# 04_GAP9_CHIP_MEM.net
KiCad netlist of a schematic drawn in Altium Designer
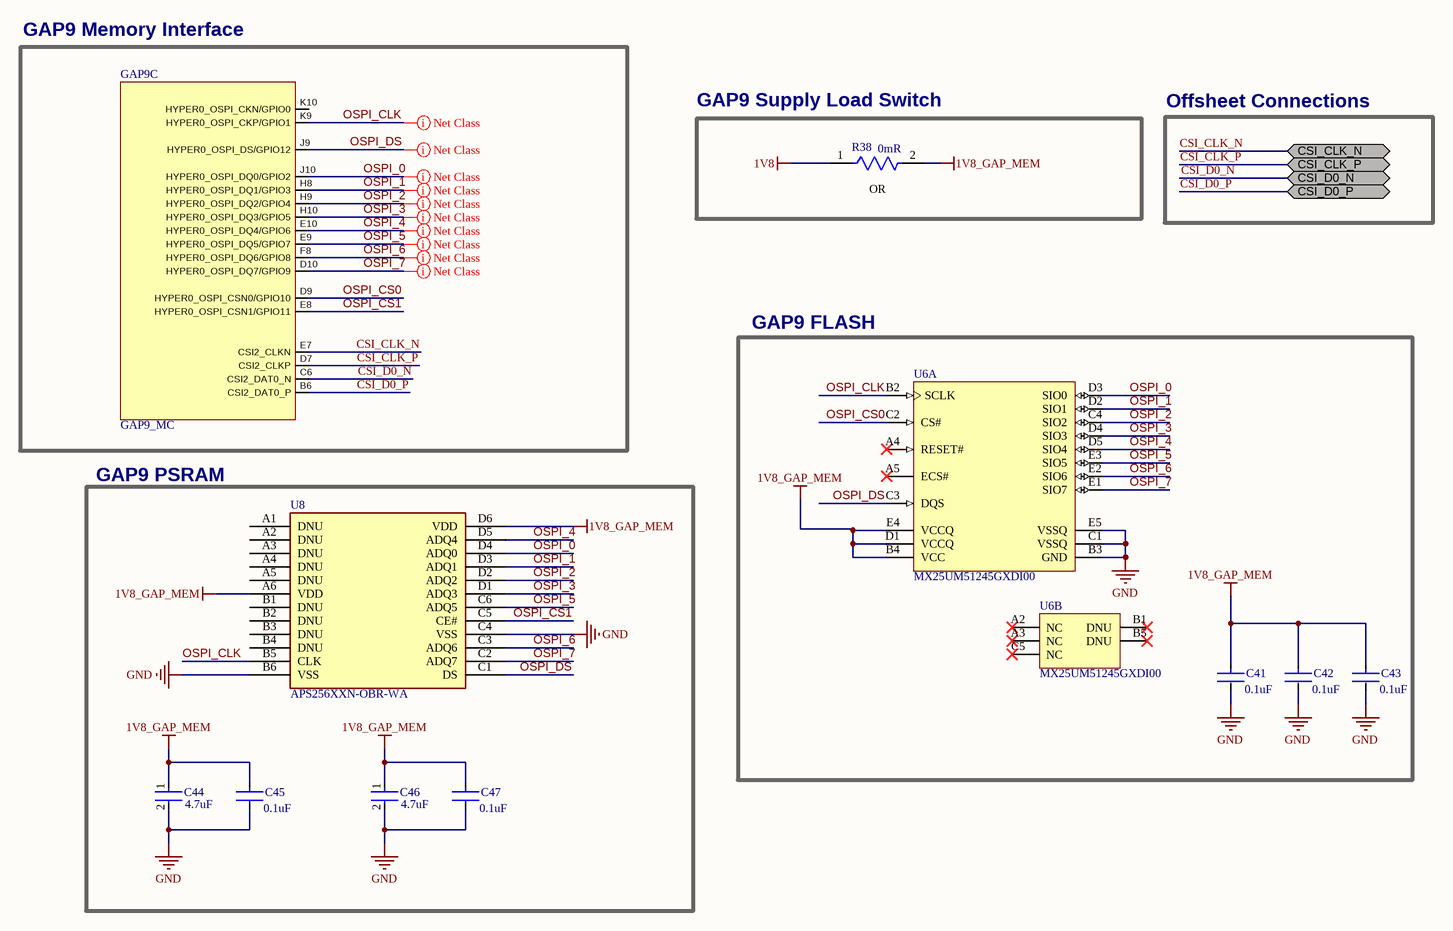
[diagram p0: 04_GAP9_CHIP_MEM.SchDoc]

(export (version "E")
  (design (tool "Eeschema 10.0.6"))
  (components
    (comp (ref "C41")
      (value "GRM033Z71C104KE14D")
      (footprint "FP-GRM033-0_03-IPC_B")
      (description "Chip Multilayer Ceramic Capacitors for General Purpose, 0201, 0.10uF, X7R, 15%, 10%, 16V")
      (fields (field (name "CAPACITANCE") "0.1uF"))
      (libsource (lib "Altium Content Vault") (part "b4654b650e69147ec39a6b967a45e02"))
    )
    (comp (ref "C42")
      (value "GRM033Z71C104KE14D")
      (footprint "FP-GRM033-0_03-IPC_B")
      (description "Chip Multilayer Ceramic Capacitors for General Purpose, 0201, 0.10uF, X7R, 15%, 10%, 16V")
      (fields (field (name "CAPACITANCE") "0.1uF"))
      (libsource (lib "Altium Content Vault") (part "b4654b650e69147ec39a6b967a45e02"))
    )
    (comp (ref "C43")
      (value "GRM033Z71C104KE14D")
      (footprint "FP-GRM033-0_03-IPC_B")
      (description "Chip Multilayer Ceramic Capacitors for General Purpose, 0201, 0.10uF, X7R, 15%, 10%, 16V")
      (fields (field (name "CAPACITANCE") "0.1uF"))
      (libsource (lib "Altium Content Vault") (part "b4654b650e69147ec39a6b967a45e02"))
    )
    (comp (ref "C44")
      (value "GRM035R60J475ME15D")
      (footprint "FP-GRM035-0_09-IPC_B")
      (description "Chip Multilayer Ceramic Capacitors for General Purpose, 0201, 4.7uF, X5R, 15%, 20%, 6.3V")
      (fields (field (name "CAPACITANCE") "4.7uF") (field (name "TOLERANCE") "20%"))
      (libsource (lib "Altium Content Vault") (part "02cd4be3c70576c341d710602a673aa"))
    )
    (comp (ref "C45")
      (value "GRM033Z71C104KE14D")
      (footprint "FP-GRM033-0_03-IPC_B")
      (description "Chip Multilayer Ceramic Capacitors for General Purpose, 0201, 0.10uF, X7R, 15%, 10%, 16V")
      (fields (field (name "CAPACITANCE") "0.1uF"))
      (libsource (lib "Altium Content Vault") (part "b4654b650e69147ec39a6b967a45e02"))
    )
    (comp (ref "C46")
      (value "GRM035R60J475ME15D")
      (footprint "FP-GRM035-0_09-IPC_B")
      (description "Chip Multilayer Ceramic Capacitors for General Purpose, 0201, 4.7uF, X5R, 15%, 20%, 6.3V")
      (fields (field (name "CAPACITANCE") "4.7uF") (field (name "TOLERANCE") "20%"))
      (libsource (lib "Altium Content Vault") (part "02cd4be3c70576c341d710602a673aa"))
    )
    (comp (ref "C47")
      (value "GRM033Z71C104KE14D")
      (footprint "FP-GRM033-0_03-IPC_B")
      (description "Chip Multilayer Ceramic Capacitors for General Purpose, 0201, 0.10uF, X7R, 15%, 10%, 16V")
      (fields (field (name "CAPACITANCE") "0.1uF"))
      (libsource (lib "Altium Content Vault") (part "b4654b650e69147ec39a6b967a45e02"))
    )
    (comp (ref "GAP9") (value "GAP9_MC") (footprint "GAP9") (libsource (lib "EEG_SchLib") (part "GAP9_MC")))
    (comp (ref "R38")
      (value "0mR")
      (footprint "FP-CRCW0402-e3-IPC_C")
      (description "RES Thick Film, 0Ω, 0.063W, 0402")
      (fields (field (name "TOLERANCE") "5%") (field (name "Comment") "CRCW04020000Z0ED"))
      (libsource (lib "Altium Content Vault") (part "1029c3af85768c4190bb7ad29bc67b5"))
    )
    (comp (ref "U6")
      (value "MX25UM51245GXDI00")
      (footprint "FBGA24_A-130")
      (description "NOR Flash Memory 512Mb 1.8V Octa I/O Serial 24-Pin BGA")
      (fields (field (name "MFR") "Macronix"))
      (libsource (lib "ETHZ Vault") (part "MX25UM51245GXDI00"))
    )
    (comp (ref "U8")
      (value "APS256XXN-OBR-WA")
      (footprint "WLCSP24")
      (description "No Description Available")
      (fields
        (field (name "MANUFACTURER_PART_NUMBER") "APS256XXN-OBR-BG")
        (field (name "COPYRIGHT") "Copyright (C) 2022 Ultra Librarian. All rights reserved.")
      )
      (libsource (lib "EEG_SchLib") (part "APS256XXN-OBR"))
    )
  )
  (nets
    (net (code "1") (name "/CSI_CLK_N") (class "Default")
      (node (ref "GAP9") (pin "E7") (pinfunction "CSI2_CLKN_E7") (pintype "passive"))
    )
    (net (code "2") (name "/CSI_CLK_P") (class "Default")
      (node (ref "GAP9") (pin "D7") (pinfunction "CSI2_CLKP_D7") (pintype "passive"))
    )
    (net (code "3") (name "/CSI_D0_N") (class "Default")
      (node (ref "GAP9") (pin "C6") (pinfunction "CSI2_DAT0_N_C6") (pintype "passive"))
    )
    (net (code "4") (name "/CSI_D0_P") (class "Default")
      (node (ref "GAP9") (pin "B6") (pinfunction "CSI2_DAT0_P_B6") (pintype "passive"))
    )
    (net (code "5") (name "/OSPI_0") (class "Default")
      (node (ref "GAP9") (pin "J10") (pinfunction "HYPER0_OSPI_DQ0/GPIO2_J10") (pintype "passive"))
      (node (ref "U6") (pin "D3") (pinfunction "SIO0_D3") (pintype "bidirectional"))
      (node (ref "U8") (pin "D4") (pinfunction "ADQ0_D4") (pintype "passive"))
    )
    (net (code "6") (name "/OSPI_1") (class "Default")
      (node (ref "GAP9") (pin "H8") (pinfunction "HYPER0_OSPI_DQ1/GPIO3_H8") (pintype "passive"))
      (node (ref "U6") (pin "D2") (pinfunction "SIO1_D2") (pintype "bidirectional"))
      (node (ref "U8") (pin "D3") (pinfunction "ADQ1_D3") (pintype "passive"))
    )
    (net (code "7") (name "/OSPI_2") (class "Default")
      (node (ref "GAP9") (pin "H9") (pinfunction "HYPER0_OSPI_DQ2/GPIO4_H9") (pintype "passive"))
      (node (ref "U6") (pin "C4") (pinfunction "SIO2_C4") (pintype "bidirectional"))
      (node (ref "U8") (pin "D2") (pinfunction "ADQ2_D2") (pintype "passive"))
    )
    (net (code "8") (name "/OSPI_3") (class "Default")
      (node (ref "GAP9") (pin "H10") (pinfunction "HYPER0_OSPI_DQ3/GPIO5_H10") (pintype "passive"))
      (node (ref "U6") (pin "D4") (pinfunction "SIO3_D4") (pintype "bidirectional"))
      (node (ref "U8") (pin "D1") (pinfunction "ADQ3_D1") (pintype "passive"))
    )
    (net (code "9") (name "/OSPI_4") (class "Default")
      (node (ref "GAP9") (pin "E10") (pinfunction "HYPER0_OSPI_DQ4/GPIO6_E10") (pintype "passive"))
      (node (ref "U6") (pin "D5") (pinfunction "SIO4_D5") (pintype "bidirectional"))
      (node (ref "U8") (pin "D5") (pinfunction "ADQ4_D5") (pintype "passive"))
    )
    (net (code "10") (name "/OSPI_5") (class "Default")
      (node (ref "GAP9") (pin "E9") (pinfunction "HYPER0_OSPI_DQ5/GPIO7_E9") (pintype "passive"))
      (node (ref "U6") (pin "E3") (pinfunction "SIO5_E3") (pintype "bidirectional"))
      (node (ref "U8") (pin "C6") (pinfunction "ADQ5_C6") (pintype "passive"))
    )
    (net (code "11") (name "/OSPI_6") (class "Default")
      (node (ref "GAP9") (pin "F8") (pinfunction "HYPER0_OSPI_DQ6/GPIO8_F8") (pintype "passive"))
      (node (ref "U6") (pin "E2") (pinfunction "SIO6_E2") (pintype "bidirectional"))
      (node (ref "U8") (pin "C3") (pinfunction "ADQ6_C3") (pintype "passive"))
    )
    (net (code "12") (name "/OSPI_7") (class "Default")
      (node (ref "GAP9") (pin "D10") (pinfunction "HYPER0_OSPI_DQ7/GPIO9_D10") (pintype "passive"))
      (node (ref "U6") (pin "E1") (pinfunction "SIO7_E1") (pintype "bidirectional"))
      (node (ref "U8") (pin "C2") (pinfunction "ADQ7_C2") (pintype "passive"))
    )
    (net (code "13") (name "/OSPI_CLK") (class "Default")
      (node (ref "GAP9") (pin "K9") (pinfunction "HYPER0_OSPI_CKP/GPIO1_K9") (pintype "passive"))
      (node (ref "U6") (pin "B2") (pinfunction "SCLK_B2") (pintype "input"))
      (node (ref "U8") (pin "B5") (pinfunction "CLK_B5") (pintype "passive"))
    )
    (net (code "14") (name "/OSPI_CS0") (class "Default")
      (node (ref "GAP9") (pin "D9") (pinfunction "HYPER0_OSPI_CSN0/GPIO10_D9") (pintype "passive"))
      (node (ref "U6") (pin "C2") (pinfunction "CS#_C2") (pintype "input"))
    )
    (net (code "15") (name "/OSPI_CS1") (class "Default")
      (node (ref "GAP9") (pin "E8") (pinfunction "HYPER0_OSPI_CSN1/GPIO11_E8") (pintype "passive"))
      (node (ref "U8") (pin "C5") (pinfunction "CE#_C5") (pintype "passive"))
    )
    (net (code "16") (name "/OSPI_DS") (class "Default")
      (node (ref "GAP9") (pin "J9") (pinfunction "HYPER0_OSPI_DS/GPIO12_J9") (pintype "passive"))
      (node (ref "U6") (pin "C3") (pinfunction "DQS_C3") (pintype "input"))
      (node (ref "U8") (pin "C1") (pinfunction "DS_C1") (pintype "passive"))
    )
    (net (code "17") (name "1V8") (class "Default")
      (node (ref "R38") (pin "1") (pinfunction "1_1") (pintype "passive"))
    )
    (net (code "18") (name "1V8_GAP_MEM") (class "Default")
      (node (ref "C41") (pin "1") (pinfunction "1_1") (pintype "passive"))
      (node (ref "C42") (pin "1") (pinfunction "1_1") (pintype "passive"))
      (node (ref "C43") (pin "1") (pinfunction "1_1") (pintype "passive"))
      (node (ref "C44") (pin "1") (pinfunction "1_1") (pintype "passive"))
      (node (ref "C45") (pin "1") (pinfunction "1_1") (pintype "passive"))
      (node (ref "C46") (pin "1") (pinfunction "1_1") (pintype "passive"))
      (node (ref "C47") (pin "1") (pinfunction "1_1") (pintype "passive"))
      (node (ref "R38") (pin "2") (pinfunction "2_2") (pintype "passive"))
      (node (ref "U6") (pin "B4") (pinfunction "VCC_B4") (pintype "power_in"))
      (node (ref "U6") (pin "D1") (pinfunction "VCCQ_D1") (pintype "power_in"))
      (node (ref "U6") (pin "E4") (pinfunction "VCCQ_E4") (pintype "power_in"))
      (node (ref "U8") (pin "A6") (pinfunction "VDD_A6") (pintype "passive"))
      (node (ref "U8") (pin "D6") (pinfunction "VDD_D6") (pintype "passive"))
    )
    (net (code "19") (name "GND") (class "Default")
      (node (ref "C41") (pin "2") (pinfunction "2_2") (pintype "passive"))
      (node (ref "C42") (pin "2") (pinfunction "2_2") (pintype "passive"))
      (node (ref "C43") (pin "2") (pinfunction "2_2") (pintype "passive"))
      (node (ref "C44") (pin "2") (pinfunction "2_2") (pintype "passive"))
      (node (ref "C45") (pin "2") (pinfunction "2_2") (pintype "passive"))
      (node (ref "C46") (pin "2") (pinfunction "2_2") (pintype "passive"))
      (node (ref "C47") (pin "2") (pinfunction "2_2") (pintype "passive"))
      (node (ref "U6") (pin "B3") (pinfunction "GND_B3") (pintype "power_in"))
      (node (ref "U6") (pin "C1") (pinfunction "VSSQ_C1") (pintype "power_in"))
      (node (ref "U6") (pin "E5") (pinfunction "VSSQ_E5") (pintype "power_in"))
      (node (ref "U8") (pin "B6") (pinfunction "VSS_B6") (pintype "passive"))
      (node (ref "U8") (pin "C4") (pinfunction "VSS_C4") (pintype "passive"))
    )
    (net (code "20") (name "unconnected-(GAP9C-HYPER0_OSPI_CKN{slash}GPIO0-PadK10)") (class "Default")
      (node (ref "GAP9") (pin "K10") (pinfunction "HYPER0_OSPI_CKN/GPIO0_K10") (pintype "passive"))
    )
    (net (code "21") (name "unconnected-(U6A-ECS#-PadA5)") (class "Default")
      (node (ref "U6") (pin "A5") (pinfunction "ECS#_A5") (pintype "open_collector+no_connect"))
    )
    (net (code "22") (name "unconnected-(U6A-RESET#-PadA4)") (class "Default")
      (node (ref "U6") (pin "A4") (pinfunction "RESET#_A4") (pintype "input+no_connect"))
    )
    (net (code "23") (name "unconnected-(U6B-DNU-PadB1)") (class "Default")
      (node (ref "U6") (pin "B1") (pinfunction "DNU_B1") (pintype "passive+no_connect"))
    )
    (net (code "24") (name "unconnected-(U6B-DNU-PadB5)") (class "Default")
      (node (ref "U6") (pin "B5") (pinfunction "DNU_B5") (pintype "passive+no_connect"))
    )
    (net (code "25") (name "unconnected-(U6B-NC-PadA2)") (class "Default")
      (node (ref "U6") (pin "A2") (pinfunction "NC_A2") (pintype "passive+no_connect"))
    )
    (net (code "26") (name "unconnected-(U6B-NC-PadA3)") (class "Default")
      (node (ref "U6") (pin "A3") (pinfunction "NC_A3") (pintype "passive+no_connect"))
    )
    (net (code "27") (name "unconnected-(U6B-NC-PadC5)") (class "Default")
      (node (ref "U6") (pin "C5") (pinfunction "NC_C5") (pintype "passive+no_connect"))
    )
    (net (code "28") (name "unconnected-(U8-DNU-PadA1)") (class "Default")
      (node (ref "U8") (pin "A1") (pinfunction "DNU_A1") (pintype "passive"))
    )
    (net (code "29") (name "unconnected-(U8-DNU-PadA2)") (class "Default")
      (node (ref "U8") (pin "A2") (pinfunction "DNU_A2") (pintype "passive"))
    )
    (net (code "30") (name "unconnected-(U8-DNU-PadA3)") (class "Default")
      (node (ref "U8") (pin "A3") (pinfunction "DNU_A3") (pintype "passive"))
    )
    (net (code "31") (name "unconnected-(U8-DNU-PadA4)") (class "Default")
      (node (ref "U8") (pin "A4") (pinfunction "DNU_A4") (pintype "passive"))
    )
    (net (code "32") (name "unconnected-(U8-DNU-PadA5)") (class "Default")
      (node (ref "U8") (pin "A5") (pinfunction "DNU_A5") (pintype "passive"))
    )
    (net (code "33") (name "unconnected-(U8-DNU-PadB1)") (class "Default")
      (node (ref "U8") (pin "B1") (pinfunction "DNU_B1") (pintype "passive"))
    )
    (net (code "34") (name "unconnected-(U8-DNU-PadB2)") (class "Default")
      (node (ref "U8") (pin "B2") (pinfunction "DNU_B2") (pintype "passive"))
    )
    (net (code "35") (name "unconnected-(U8-DNU-PadB3)") (class "Default")
      (node (ref "U8") (pin "B3") (pinfunction "DNU_B3") (pintype "passive"))
    )
    (net (code "36") (name "unconnected-(U8-DNU-PadB4)") (class "Default")
      (node (ref "U8") (pin "B4") (pinfunction "DNU_B4") (pintype "passive"))
    )
  )
)
